# debugBoard.net
KiCad netlist of a schematic drawn in EAGLE
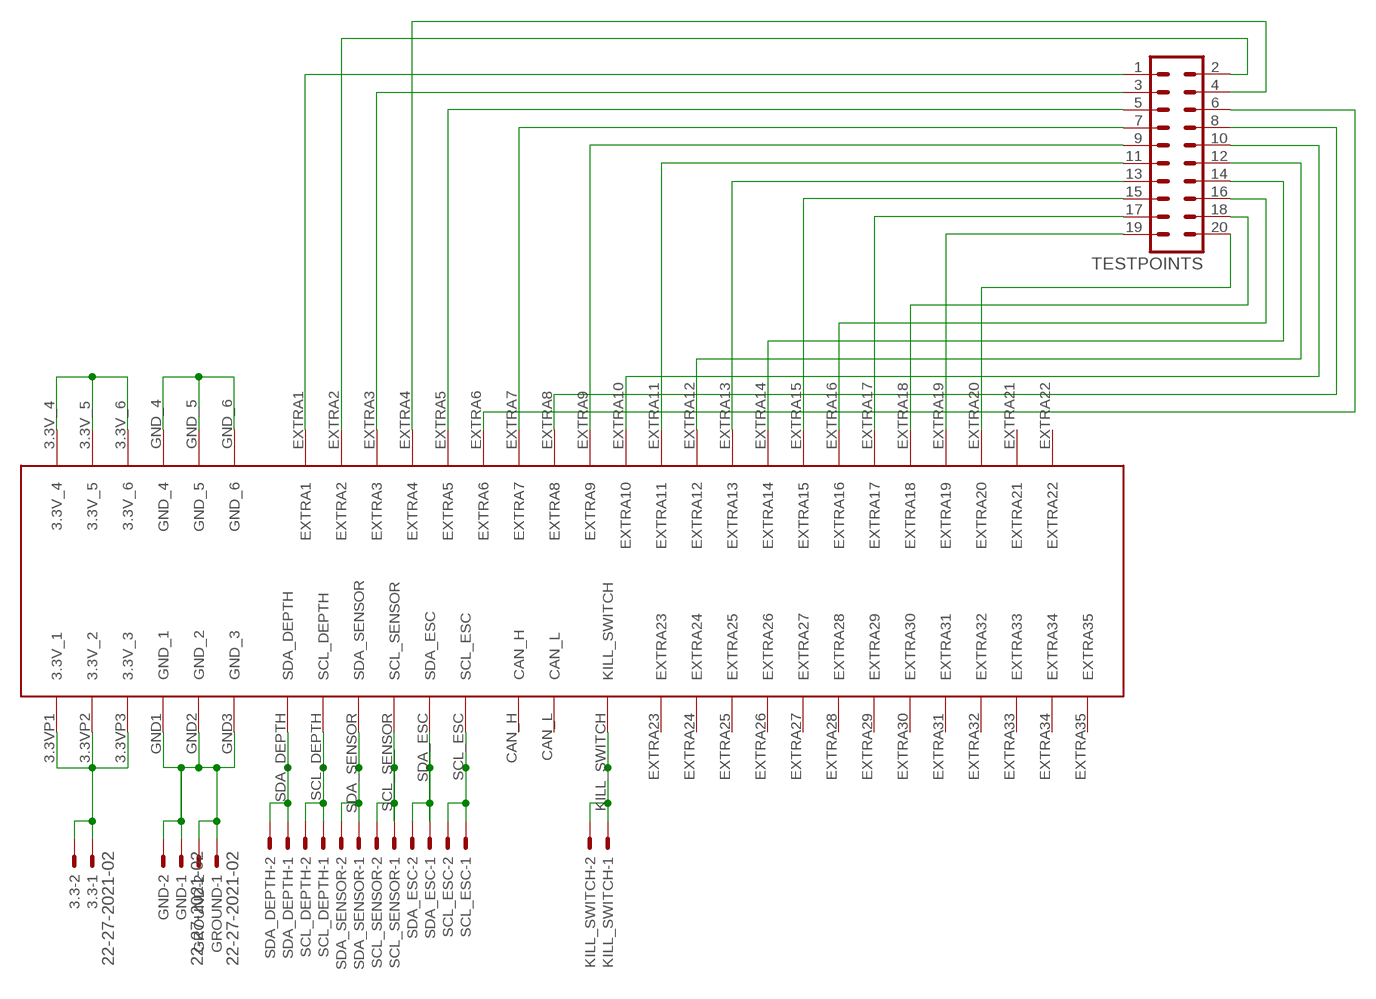
[diagram p0: schematic, sheet 1]

(export (version "E")
  (design (tool "Eeschema 10.0.6"))
  (components
    (comp (ref "3.3")
      (value "22-27-2021-02")
      (footprint "eagle-import:6410-02")
      (libsource (lib "eagle-import") (part "22-?-0227-2021"))
    )
    (comp (ref "GND")
      (value "22-27-2021-02")
      (footprint "eagle-import:6410-02")
      (libsource (lib "eagle-import") (part "22-?-0227-2021"))
    )
    (comp (ref "GROUND")
      (value "22-27-2021-02")
      (footprint "eagle-import:6410-02")
      (libsource (lib "eagle-import") (part "22-?-0227-2021"))
    )
    (comp (ref "KILL_SWITCH")
      (value "22-27-2021-02")
      (footprint "eagle-import:6410-02")
      (libsource (lib "eagle-import") (part "22-?-0227-2021"))
    )
    (comp (ref "SCL_DEPTH")
      (value "22-27-2021-02")
      (footprint "eagle-import:6410-02")
      (libsource (lib "eagle-import") (part "22-?-0227-2021"))
    )
    (comp (ref "SCL_ESC")
      (value "22-27-2021-02")
      (footprint "eagle-import:6410-02")
      (libsource (lib "eagle-import") (part "22-?-0227-2021"))
    )
    (comp (ref "SCL_SENSOR")
      (value "22-27-2021-02")
      (footprint "eagle-import:6410-02")
      (libsource (lib "eagle-import") (part "22-?-0227-2021"))
    )
    (comp (ref "SDA_DEPTH")
      (value "22-27-2021-02")
      (footprint "eagle-import:6410-02")
      (libsource (lib "eagle-import") (part "22-?-0227-2021"))
    )
    (comp (ref "SDA_ESC")
      (value "22-27-2021-02")
      (footprint "eagle-import:6410-02")
      (libsource (lib "eagle-import") (part "22-?-0227-2021"))
    )
    (comp (ref "SDA_SENSOR")
      (value "22-27-2021-02")
      (footprint "eagle-import:6410-02")
      (libsource (lib "eagle-import") (part "22-?-0227-2021"))
    )
    (comp (ref "TESTPOINTS")
      (value "MA10-2")
      (footprint "eagle-import:MA10-2")
      (libsource (lib "eagle-import") (part "MA10-2"))
    )
    (comp (ref "U$1")
      (value "5530843")
      (footprint "eagle-import:5530843-6-BOARDFINGERS")
      (libsource (lib "eagle-import") (part "5530843"))
    )
  )
  (nets
    (net (code "1") (name "/3.3V") (class "Default")
      (node (ref "3.3") (pin "1") (pinfunction "S_1") (pintype "passive"))
      (node (ref "3.3") (pin "2") (pinfunction "S_2") (pintype "passive"))
      (node (ref "U$1") (pin "3.3VP1") (pinfunction "3.3V_1_3.3VP1") (pintype "bidirectional"))
      (node (ref "U$1") (pin "3.3VP2") (pinfunction "3.3V_2_3.3VP2") (pintype "bidirectional"))
      (node (ref "U$1") (pin "3.3VP3") (pinfunction "3.3V_3_3.3VP3") (pintype "bidirectional"))
      (node (ref "U$1") (pin "3.3V_4") (pinfunction "3.3V_4_3.3V_4") (pintype "bidirectional"))
      (node (ref "U$1") (pin "3.3V_5") (pinfunction "3.3V_5_3.3V_5") (pintype "bidirectional"))
      (node (ref "U$1") (pin "3.3V_6") (pinfunction "3.3V_6_3.3V_6") (pintype "bidirectional"))
    )
    (net (code "2") (name "/GND") (class "Default")
      (node (ref "GND") (pin "1") (pinfunction "S_1") (pintype "passive"))
      (node (ref "GND") (pin "2") (pinfunction "S_2") (pintype "passive"))
      (node (ref "GROUND") (pin "1") (pinfunction "S_1") (pintype "passive"))
      (node (ref "GROUND") (pin "2") (pinfunction "S_2") (pintype "passive"))
      (node (ref "U$1") (pin "GND1") (pinfunction "GND_1_GND1") (pintype "bidirectional"))
      (node (ref "U$1") (pin "GND2") (pinfunction "GND_2_GND2") (pintype "bidirectional"))
      (node (ref "U$1") (pin "GND3") (pinfunction "GND_3_GND3") (pintype "bidirectional"))
      (node (ref "U$1") (pin "GND_4") (pinfunction "GND_4_GND_4") (pintype "bidirectional"))
      (node (ref "U$1") (pin "GND_5") (pinfunction "GND_5_GND_5") (pintype "bidirectional"))
      (node (ref "U$1") (pin "GND_6") (pinfunction "GND_6_GND_6") (pintype "bidirectional"))
    )
    (net (code "3") (name "Net-(KILL_SWITCHA-S)") (class "Default")
      (node (ref "KILL_SWITCH") (pin "1") (pinfunction "S_1") (pintype "passive"))
      (node (ref "KILL_SWITCH") (pin "2") (pinfunction "S_2") (pintype "passive"))
      (node (ref "U$1") (pin "KILL_SWITCH") (pinfunction "KILL_SWITCH_KILL_SWITCH") (pintype "bidirectional"))
    )
    (net (code "4") (name "Net-(SCL_DEPTHA-S)") (class "Default")
      (node (ref "SCL_DEPTH") (pin "1") (pinfunction "S_1") (pintype "passive"))
      (node (ref "SCL_DEPTH") (pin "2") (pinfunction "S_2") (pintype "passive"))
      (node (ref "U$1") (pin "SCL_DEPTH") (pinfunction "SCL_DEPTH_SCL_DEPTH") (pintype "bidirectional"))
    )
    (net (code "5") (name "Net-(SCL_ESCA-S)") (class "Default")
      (node (ref "SCL_ESC") (pin "1") (pinfunction "S_1") (pintype "passive"))
      (node (ref "SCL_ESC") (pin "2") (pinfunction "S_2") (pintype "passive"))
      (node (ref "U$1") (pin "SCL_ESC") (pinfunction "SCL_ESC_SCL_ESC") (pintype "bidirectional"))
    )
    (net (code "6") (name "Net-(SCL_SENSORA-S)") (class "Default")
      (node (ref "SCL_SENSOR") (pin "1") (pinfunction "S_1") (pintype "passive"))
      (node (ref "SCL_SENSOR") (pin "2") (pinfunction "S_2") (pintype "passive"))
      (node (ref "U$1") (pin "SCL_SENSOR") (pinfunction "SCL_SENSOR_SCL_SENSOR") (pintype "bidirectional"))
    )
    (net (code "7") (name "Net-(SDA_DEPTHA-S)") (class "Default")
      (node (ref "SDA_DEPTH") (pin "1") (pinfunction "S_1") (pintype "passive"))
      (node (ref "SDA_DEPTH") (pin "2") (pinfunction "S_2") (pintype "passive"))
      (node (ref "U$1") (pin "SDA_DEPTH") (pinfunction "SDA_DEPTH_SDA_DEPTH") (pintype "bidirectional"))
    )
    (net (code "8") (name "Net-(SDA_ESCA-S)") (class "Default")
      (node (ref "SDA_ESC") (pin "1") (pinfunction "S_1") (pintype "passive"))
      (node (ref "SDA_ESC") (pin "2") (pinfunction "S_2") (pintype "passive"))
      (node (ref "U$1") (pin "SDA_ESC") (pinfunction "SDA_ESC_SDA_ESC") (pintype "bidirectional"))
    )
    (net (code "9") (name "Net-(SDA_SENSORA-S)") (class "Default")
      (node (ref "SDA_SENSOR") (pin "1") (pinfunction "S_1") (pintype "passive"))
      (node (ref "SDA_SENSOR") (pin "2") (pinfunction "S_2") (pintype "passive"))
      (node (ref "U$1") (pin "SDA_SENSOR") (pinfunction "SDA_SENSOR_SDA_SENSOR") (pintype "bidirectional"))
    )
    (net (code "10") (name "Net-(TESTPOINTS-Pad1)") (class "Default")
      (node (ref "TESTPOINTS") (pin "1") (pinfunction "1_1") (pintype "passive"))
      (node (ref "U$1") (pin "EXTRA1") (pinfunction "EXTRA1_EXTRA1") (pintype "bidirectional"))
    )
    (net (code "11") (name "Net-(TESTPOINTS-Pad2)") (class "Default")
      (node (ref "TESTPOINTS") (pin "2") (pinfunction "2_2") (pintype "passive"))
      (node (ref "U$1") (pin "EXTRA2") (pinfunction "EXTRA2_EXTRA2") (pintype "bidirectional"))
    )
    (net (code "12") (name "Net-(TESTPOINTS-Pad3)") (class "Default")
      (node (ref "TESTPOINTS") (pin "3") (pinfunction "3_3") (pintype "passive"))
      (node (ref "U$1") (pin "EXTRA3") (pinfunction "EXTRA3_EXTRA3") (pintype "bidirectional"))
    )
    (net (code "13") (name "Net-(TESTPOINTS-Pad4)") (class "Default")
      (node (ref "TESTPOINTS") (pin "4") (pinfunction "4_4") (pintype "passive"))
      (node (ref "U$1") (pin "EXTRA4") (pinfunction "EXTRA4_EXTRA4") (pintype "bidirectional"))
    )
    (net (code "14") (name "Net-(TESTPOINTS-Pad5)") (class "Default")
      (node (ref "TESTPOINTS") (pin "5") (pinfunction "5_5") (pintype "passive"))
      (node (ref "U$1") (pin "EXTRA5") (pinfunction "EXTRA5_EXTRA5") (pintype "bidirectional"))
    )
    (net (code "15") (name "Net-(TESTPOINTS-Pad6)") (class "Default")
      (node (ref "TESTPOINTS") (pin "6") (pinfunction "6_6") (pintype "passive"))
      (node (ref "U$1") (pin "EXTRA6") (pinfunction "EXTRA6_EXTRA6") (pintype "bidirectional"))
    )
    (net (code "16") (name "Net-(TESTPOINTS-Pad7)") (class "Default")
      (node (ref "TESTPOINTS") (pin "7") (pinfunction "7_7") (pintype "passive"))
      (node (ref "U$1") (pin "EXTRA7") (pinfunction "EXTRA7_EXTRA7") (pintype "bidirectional"))
    )
    (net (code "17") (name "Net-(TESTPOINTS-Pad8)") (class "Default")
      (node (ref "TESTPOINTS") (pin "8") (pinfunction "8_8") (pintype "passive"))
      (node (ref "U$1") (pin "EXTRA8") (pinfunction "EXTRA8_EXTRA8") (pintype "bidirectional"))
    )
    (net (code "18") (name "Net-(TESTPOINTS-Pad9)") (class "Default")
      (node (ref "TESTPOINTS") (pin "9") (pinfunction "9_9") (pintype "passive"))
      (node (ref "U$1") (pin "EXTRA9") (pinfunction "EXTRA9_EXTRA9") (pintype "bidirectional"))
    )
    (net (code "19") (name "Net-(TESTPOINTS-Pad10)") (class "Default")
      (node (ref "TESTPOINTS") (pin "10") (pinfunction "10_10") (pintype "passive"))
      (node (ref "U$1") (pin "EXTRA10") (pinfunction "EXTRA10_EXTRA10") (pintype "bidirectional"))
    )
    (net (code "20") (name "Net-(TESTPOINTS-Pad11)") (class "Default")
      (node (ref "TESTPOINTS") (pin "11") (pinfunction "11_11") (pintype "passive"))
      (node (ref "U$1") (pin "EXTRA11") (pinfunction "EXTRA11_EXTRA11") (pintype "bidirectional"))
    )
    (net (code "21") (name "Net-(TESTPOINTS-Pad12)") (class "Default")
      (node (ref "TESTPOINTS") (pin "12") (pinfunction "12_12") (pintype "passive"))
      (node (ref "U$1") (pin "EXTRA12") (pinfunction "EXTRA12_EXTRA12") (pintype "bidirectional"))
    )
    (net (code "22") (name "Net-(TESTPOINTS-Pad13)") (class "Default")
      (node (ref "TESTPOINTS") (pin "13") (pinfunction "13_13") (pintype "passive"))
      (node (ref "U$1") (pin "EXTRA13") (pinfunction "EXTRA13_EXTRA13") (pintype "bidirectional"))
    )
    (net (code "23") (name "Net-(TESTPOINTS-Pad14)") (class "Default")
      (node (ref "TESTPOINTS") (pin "14") (pinfunction "14_14") (pintype "passive"))
      (node (ref "U$1") (pin "EXTRA14") (pinfunction "EXTRA14_EXTRA14") (pintype "bidirectional"))
    )
    (net (code "24") (name "Net-(TESTPOINTS-Pad15)") (class "Default")
      (node (ref "TESTPOINTS") (pin "15") (pinfunction "15_15") (pintype "passive"))
      (node (ref "U$1") (pin "EXTRA15") (pinfunction "EXTRA15_EXTRA15") (pintype "bidirectional"))
    )
    (net (code "25") (name "Net-(TESTPOINTS-Pad16)") (class "Default")
      (node (ref "TESTPOINTS") (pin "16") (pinfunction "16_16") (pintype "passive"))
      (node (ref "U$1") (pin "EXTRA16") (pinfunction "EXTRA16_EXTRA16") (pintype "bidirectional"))
    )
    (net (code "26") (name "Net-(TESTPOINTS-Pad17)") (class "Default")
      (node (ref "TESTPOINTS") (pin "17") (pinfunction "17_17") (pintype "passive"))
      (node (ref "U$1") (pin "EXTRA17") (pinfunction "EXTRA17_EXTRA17") (pintype "bidirectional"))
    )
    (net (code "27") (name "Net-(TESTPOINTS-Pad18)") (class "Default")
      (node (ref "TESTPOINTS") (pin "18") (pinfunction "18_18") (pintype "passive"))
      (node (ref "U$1") (pin "EXTRA18") (pinfunction "EXTRA18_EXTRA18") (pintype "bidirectional"))
    )
    (net (code "28") (name "Net-(TESTPOINTS-Pad19)") (class "Default")
      (node (ref "TESTPOINTS") (pin "19") (pinfunction "19_19") (pintype "passive"))
      (node (ref "U$1") (pin "EXTRA19") (pinfunction "EXTRA19_EXTRA19") (pintype "bidirectional"))
    )
    (net (code "29") (name "Net-(TESTPOINTS-Pad20)") (class "Default")
      (node (ref "TESTPOINTS") (pin "20") (pinfunction "20_20") (pintype "passive"))
      (node (ref "U$1") (pin "EXTRA20") (pinfunction "EXTRA20_EXTRA20") (pintype "bidirectional"))
    )
    (net (code "30") (name "unconnected-(U$1-PadCAN_H)") (class "Default")
      (node (ref "U$1") (pin "CAN_H") (pinfunction "CAN_H_CAN_H") (pintype "bidirectional"))
    )
    (net (code "31") (name "unconnected-(U$1-PadCAN_L)") (class "Default")
      (node (ref "U$1") (pin "CAN_L") (pinfunction "CAN_L_CAN_L") (pintype "bidirectional"))
    )
    (net (code "32") (name "unconnected-(U$1-PadEXTRA21)") (class "Default")
      (node (ref "U$1") (pin "EXTRA21") (pinfunction "EXTRA21_EXTRA21") (pintype "bidirectional"))
    )
    (net (code "33") (name "unconnected-(U$1-PadEXTRA22)") (class "Default")
      (node (ref "U$1") (pin "EXTRA22") (pinfunction "EXTRA22_EXTRA22") (pintype "bidirectional"))
    )
    (net (code "34") (name "unconnected-(U$1-PadEXTRA23)") (class "Default")
      (node (ref "U$1") (pin "EXTRA23") (pinfunction "EXTRA23_EXTRA23") (pintype "bidirectional"))
    )
    (net (code "35") (name "unconnected-(U$1-PadEXTRA24)") (class "Default")
      (node (ref "U$1") (pin "EXTRA24") (pinfunction "EXTRA24_EXTRA24") (pintype "bidirectional"))
    )
    (net (code "36") (name "unconnected-(U$1-PadEXTRA25)") (class "Default")
      (node (ref "U$1") (pin "EXTRA25") (pinfunction "EXTRA25_EXTRA25") (pintype "bidirectional"))
    )
    (net (code "37") (name "unconnected-(U$1-PadEXTRA26)") (class "Default")
      (node (ref "U$1") (pin "EXTRA26") (pinfunction "EXTRA26_EXTRA26") (pintype "bidirectional"))
    )
    (net (code "38") (name "unconnected-(U$1-PadEXTRA27)") (class "Default")
      (node (ref "U$1") (pin "EXTRA27") (pinfunction "EXTRA27_EXTRA27") (pintype "bidirectional"))
    )
    (net (code "39") (name "unconnected-(U$1-PadEXTRA28)") (class "Default")
      (node (ref "U$1") (pin "EXTRA28") (pinfunction "EXTRA28_EXTRA28") (pintype "bidirectional"))
    )
    (net (code "40") (name "unconnected-(U$1-PadEXTRA29)") (class "Default")
      (node (ref "U$1") (pin "EXTRA29") (pinfunction "EXTRA29_EXTRA29") (pintype "bidirectional"))
    )
    (net (code "41") (name "unconnected-(U$1-PadEXTRA30)") (class "Default")
      (node (ref "U$1") (pin "EXTRA30") (pinfunction "EXTRA30_EXTRA30") (pintype "bidirectional"))
    )
    (net (code "42") (name "unconnected-(U$1-PadEXTRA31)") (class "Default")
      (node (ref "U$1") (pin "EXTRA31") (pinfunction "EXTRA31_EXTRA31") (pintype "bidirectional"))
    )
    (net (code "43") (name "unconnected-(U$1-PadEXTRA32)") (class "Default")
      (node (ref "U$1") (pin "EXTRA32") (pinfunction "EXTRA32_EXTRA32") (pintype "bidirectional"))
    )
    (net (code "44") (name "unconnected-(U$1-PadEXTRA33)") (class "Default")
      (node (ref "U$1") (pin "EXTRA33") (pinfunction "EXTRA33_EXTRA33") (pintype "bidirectional"))
    )
    (net (code "45") (name "unconnected-(U$1-PadEXTRA34)") (class "Default")
      (node (ref "U$1") (pin "EXTRA34") (pinfunction "EXTRA34_EXTRA34") (pintype "bidirectional"))
    )
    (net (code "46") (name "unconnected-(U$1-PadEXTRA35)") (class "Default")
      (node (ref "U$1") (pin "EXTRA35") (pinfunction "EXTRA35_EXTRA35") (pintype "bidirectional"))
    )
  )
)
